# Ambi-Light.net
KiCad netlist of a schematic drawn in EAGLE
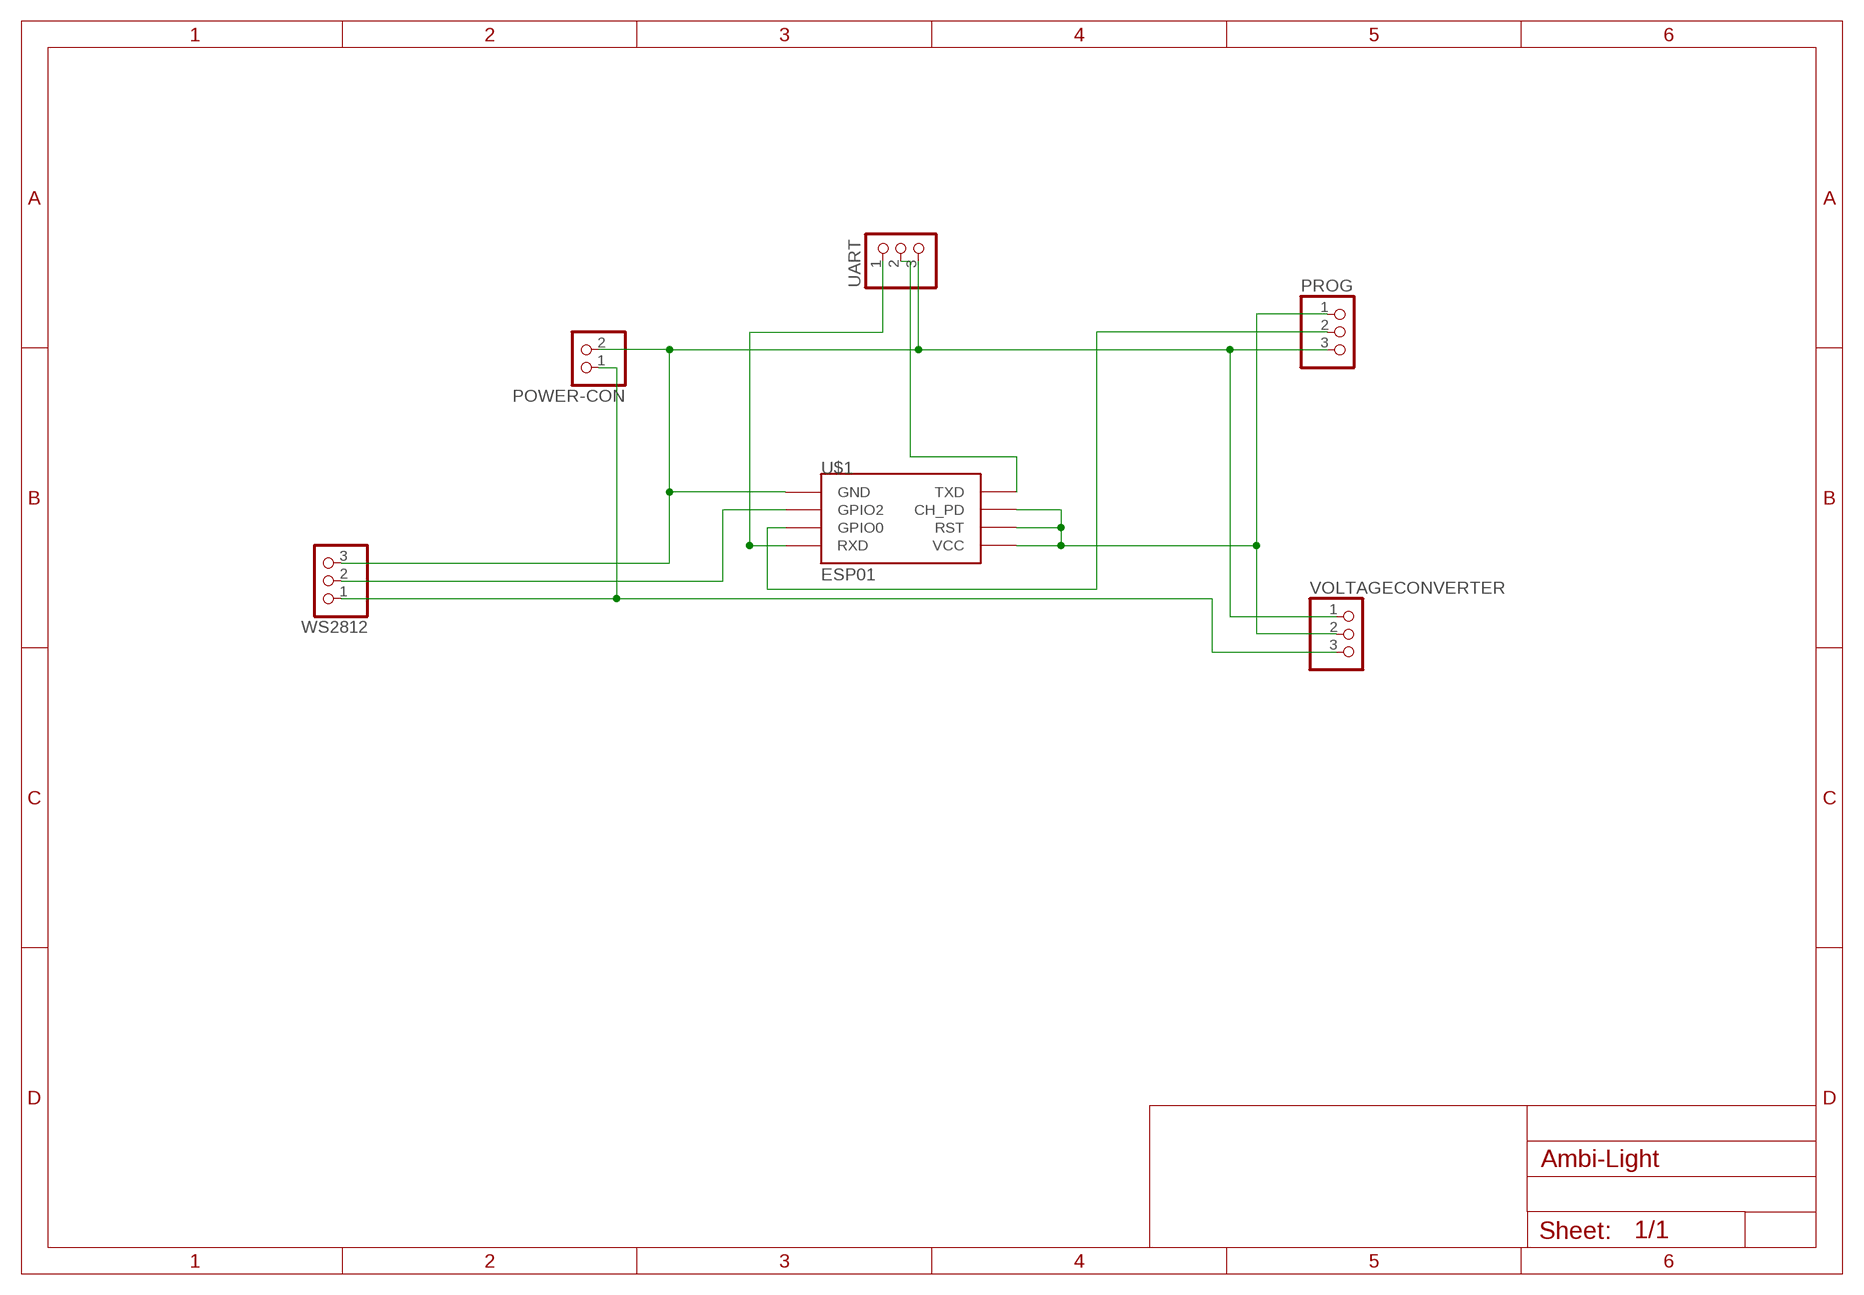
[diagram p0: schematic, sheet 1]

(export (version "E")
  (design (tool "Eeschema 10.0.6"))
  (components
    (comp (ref "POWER-CON")
      (value "PINHD-1X2")
      (footprint "eagle-import:1X02")
      (libsource (lib "eagle-import") (part "PINHD-1X2"))
    )
    (comp (ref "PROG")
      (value "PINHD-1X3")
      (footprint "eagle-import:1X03")
      (libsource (lib "eagle-import") (part "PINHD-1X3"))
    )
    (comp (ref "U$1")
      (value "ESP01")
      (footprint "eagle-import:ESP01")
      (libsource (lib "eagle-import") (part "ESP01"))
    )
    (comp (ref "UART")
      (value "PINHD-1X3")
      (footprint "eagle-import:1X03")
      (libsource (lib "eagle-import") (part "PINHD-1X3"))
    )
    (comp (ref "VOLTAGECONVERTER")
      (value "PINHD-1X3")
      (footprint "eagle-import:1X03")
      (libsource (lib "eagle-import") (part "PINHD-1X3"))
    )
    (comp (ref "WS2812")
      (value "PINHD-1X3")
      (footprint "eagle-import:1X03")
      (libsource (lib "eagle-import") (part "PINHD-1X3"))
    )
  )
  (nets
    (net (code "1") (name "Net-(POWER-CON-Pad1)") (class "Default")
      (node (ref "POWER-CON") (pin "1") (pinfunction "1_1") (pintype "passive"))
      (node (ref "VOLTAGECONVERTER") (pin "3") (pinfunction "3_3") (pintype "passive"))
      (node (ref "WS2812") (pin "1") (pinfunction "1_1") (pintype "passive"))
    )
    (net (code "2") (name "Net-(POWER-CON-Pad2)") (class "Default")
      (node (ref "POWER-CON") (pin "2") (pinfunction "2_2") (pintype "passive"))
      (node (ref "PROG") (pin "3") (pinfunction "3_3") (pintype "passive"))
      (node (ref "U$1") (pin "GND") (pinfunction "GND_GND") (pintype "bidirectional"))
      (node (ref "UART") (pin "3") (pinfunction "3_3") (pintype "passive"))
      (node (ref "VOLTAGECONVERTER") (pin "1") (pinfunction "1_1") (pintype "passive"))
      (node (ref "WS2812") (pin "3") (pinfunction "3_3") (pintype "passive"))
    )
    (net (code "3") (name "Net-(PROG-Pad1)") (class "Default")
      (node (ref "PROG") (pin "1") (pinfunction "1_1") (pintype "passive"))
      (node (ref "U$1") (pin "CH_PD") (pinfunction "CH_PD_CH_PD") (pintype "bidirectional"))
      (node (ref "U$1") (pin "RST") (pinfunction "RST_RST") (pintype "bidirectional"))
      (node (ref "U$1") (pin "VCC") (pinfunction "VCC_VCC") (pintype "bidirectional"))
      (node (ref "VOLTAGECONVERTER") (pin "2") (pinfunction "2_2") (pintype "passive"))
    )
    (net (code "4") (name "Net-(PROG-Pad2)") (class "Default")
      (node (ref "PROG") (pin "2") (pinfunction "2_2") (pintype "passive"))
      (node (ref "U$1") (pin "GPIO0") (pinfunction "GPIO0_GPIO0") (pintype "bidirectional"))
    )
    (net (code "5") (name "Net-(U$1-PadGPIO2)") (class "Default")
      (node (ref "U$1") (pin "GPIO2") (pinfunction "GPIO2_GPIO2") (pintype "bidirectional"))
      (node (ref "WS2812") (pin "2") (pinfunction "2_2") (pintype "passive"))
    )
    (net (code "6") (name "Net-(U$1-RXD)") (class "Default")
      (node (ref "U$1") (pin "RX") (pinfunction "RXD_RX") (pintype "bidirectional"))
      (node (ref "UART") (pin "1") (pinfunction "1_1") (pintype "passive"))
    )
    (net (code "7") (name "Net-(U$1-TXD)") (class "Default")
      (node (ref "U$1") (pin "TX") (pinfunction "TXD_TX") (pintype "bidirectional"))
      (node (ref "UART") (pin "2") (pinfunction "2_2") (pintype "passive"))
    )
  )
)
